# SilentStepStick-TMC2100_v20.net
KiCad netlist of a schematic drawn in EAGLE
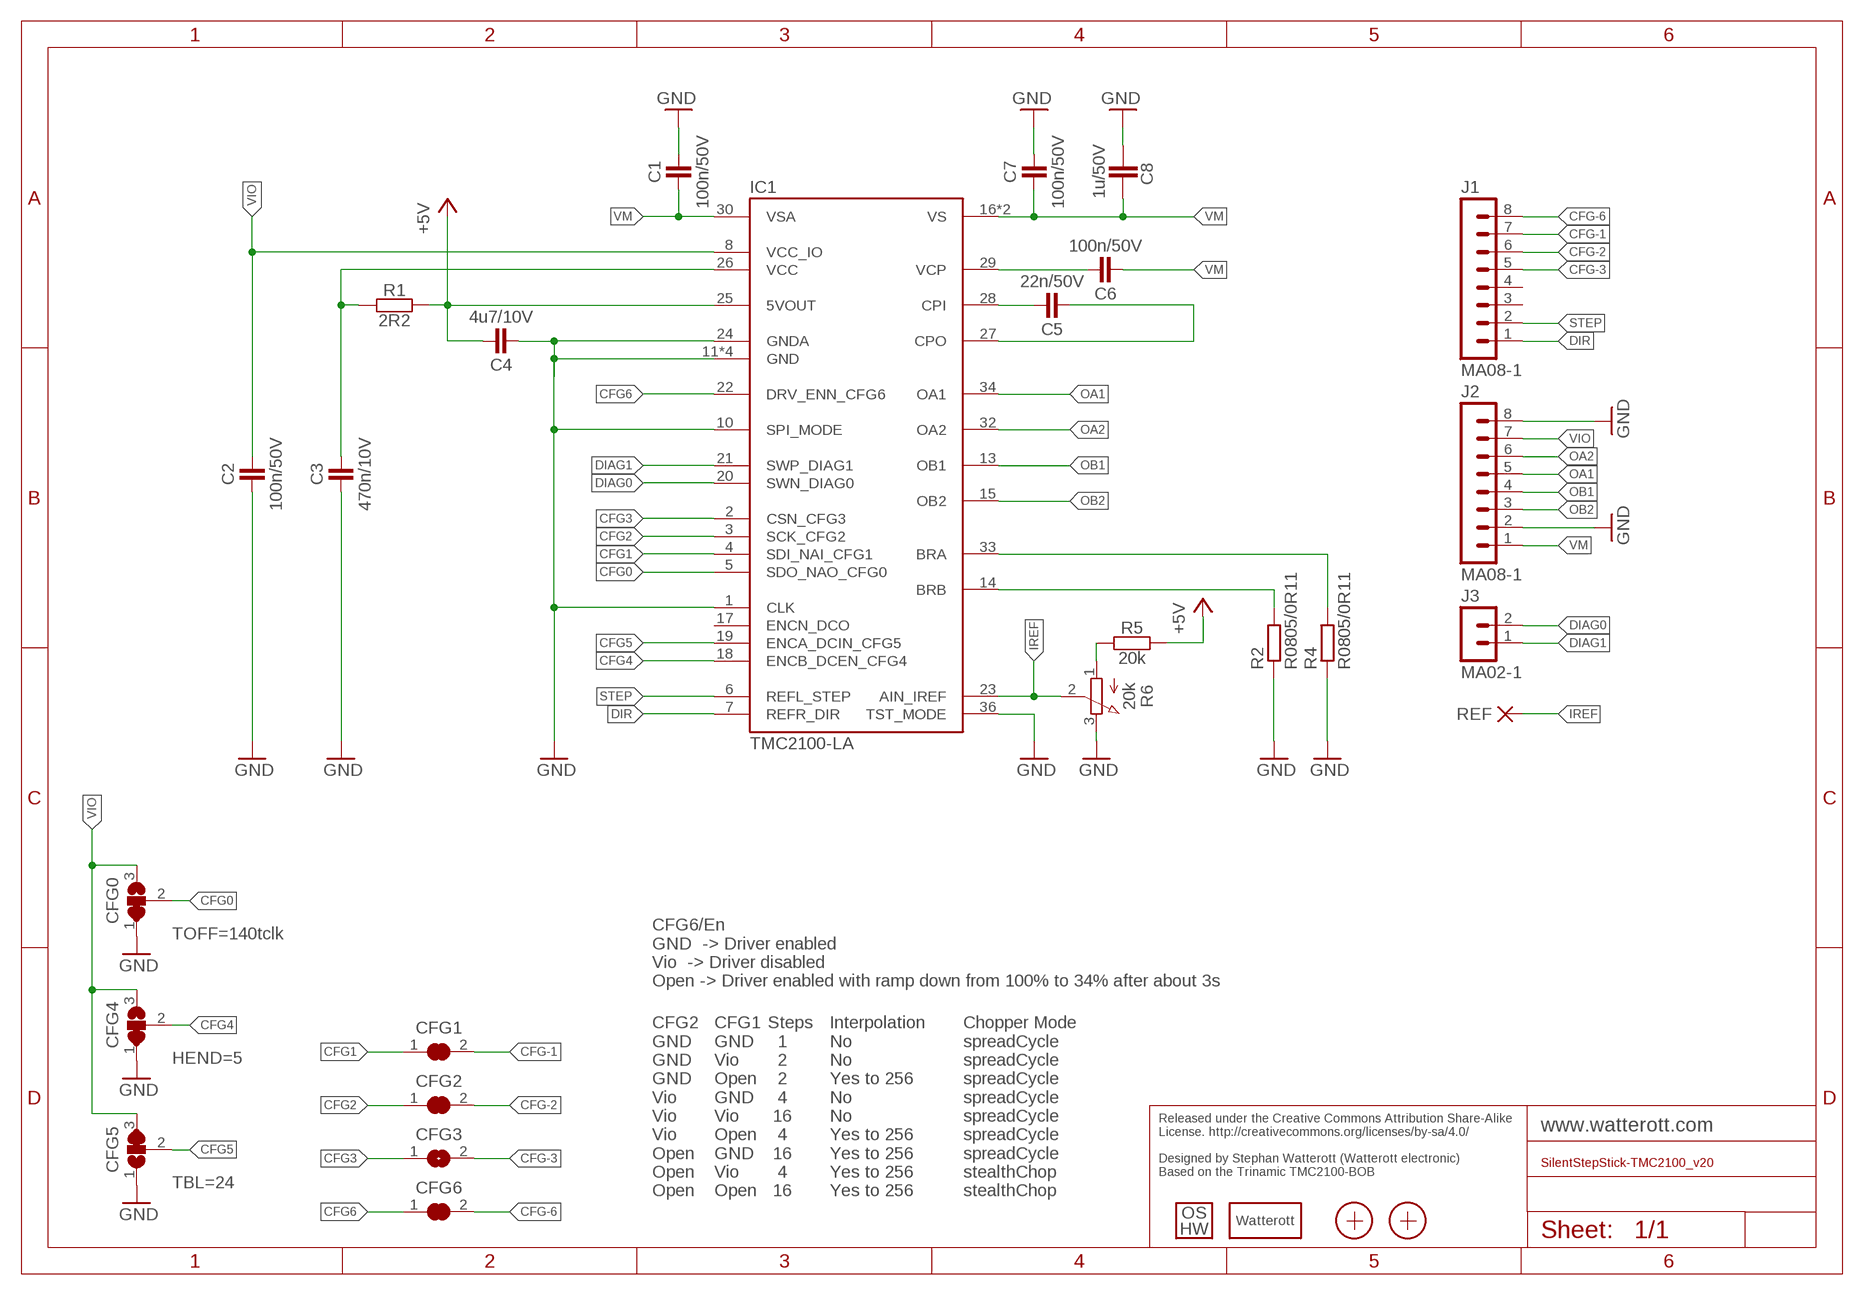
[diagram p0: schematic, sheet 1]

(export (version "E")
  (design (tool "Eeschema 10.0.6"))
  (components
    (comp (ref "C1")
      (value "100n/50V")
      (footprint "eagle-import:C0402")
      (libsource (lib "eagle-import") (part "CAPACITOR-0402"))
    )
    (comp (ref "C2")
      (value "100n/50V")
      (footprint "eagle-import:C0402")
      (libsource (lib "eagle-import") (part "CAPACITOR-0402"))
    )
    (comp (ref "C3")
      (value "470n/10V")
      (footprint "eagle-import:C0402")
      (libsource (lib "eagle-import") (part "CAPACITOR-0402"))
    )
    (comp (ref "C4")
      (value "4u7/10V")
      (footprint "eagle-import:C0402")
      (libsource (lib "eagle-import") (part "CAPACITOR-0402"))
    )
    (comp (ref "C5")
      (value "22n/50V")
      (footprint "eagle-import:C0402")
      (libsource (lib "eagle-import") (part "CAPACITOR-0402"))
    )
    (comp (ref "C6")
      (value "100n/50V")
      (footprint "eagle-import:C0402")
      (libsource (lib "eagle-import") (part "CAPACITOR-0402"))
    )
    (comp (ref "C7")
      (value "100n/50V")
      (footprint "eagle-import:C0402")
      (libsource (lib "eagle-import") (part "CAPACITOR-0402"))
    )
    (comp (ref "C8")
      (value "1u/50V")
      (footprint "eagle-import:C0603")
      (libsource (lib "eagle-import") (part "C-EUC0603"))
    )
    (comp (ref "CFG0")
      (value "JUMPER3-0201")
      (footprint "eagle-import:JUMPER3-0201")
      (libsource (lib "eagle-import") (part "JUMPER3-0201"))
    )
    (comp (ref "CFG1")
      (value "JUMPER2-0201")
      (footprint "eagle-import:JUMPER2-0201")
      (libsource (lib "eagle-import") (part "JUMPER2-0201"))
    )
    (comp (ref "CFG2")
      (value "JUMPER2-0201")
      (footprint "eagle-import:JUMPER2-0201")
      (libsource (lib "eagle-import") (part "JUMPER2-0201"))
    )
    (comp (ref "CFG3")
      (value "JUMPER2-0201")
      (footprint "eagle-import:JUMPER2-0201")
      (libsource (lib "eagle-import") (part "JUMPER2-0201"))
    )
    (comp (ref "CFG4")
      (value "JUMPER3-0201")
      (footprint "eagle-import:JUMPER3-0201")
      (libsource (lib "eagle-import") (part "JUMPER3-0201"))
    )
    (comp (ref "CFG5")
      (value "JUMPER3-0201")
      (footprint "eagle-import:JUMPER3-0201")
      (libsource (lib "eagle-import") (part "JUMPER3-0201"))
    )
    (comp (ref "CFG6")
      (value "JUMPER2-0201")
      (footprint "eagle-import:JUMPER2-0201")
      (libsource (lib "eagle-import") (part "JUMPER2-0201"))
    )
    (comp (ref "IC1")
      (value "TMC2100-LA")
      (footprint "eagle-import:QFN36-PAD")
      (libsource (lib "eagle-import") (part "TMC21X0-LA"))
    )
    (comp (ref "J1")
      (value "MA08-1")
      (footprint "eagle-import:MA08-1")
      (libsource (lib "eagle-import") (part "MA08-1"))
    )
    (comp (ref "J2")
      (value "MA08-1")
      (footprint "eagle-import:MA08-1")
      (libsource (lib "eagle-import") (part "MA08-1"))
    )
    (comp (ref "J3")
      (value "MA02-1")
      (footprint "eagle-import:MA02-1")
      (libsource (lib "eagle-import") (part "MA02-1"))
    )
    (comp (ref "LOGO3")
      (value "LOGO_SPARK-2")
      (footprint "eagle-import:SPARK_2MM")
      (libsource (lib "eagle-import") (part "LOGO_SPARK-2"))
    )
    (comp (ref "LOGO4")
      (value "LOGO_OSHW-2")
      (footprint "eagle-import:OSHW_2MM")
      (libsource (lib "eagle-import") (part "LOGO_OSHW-2"))
    )
    (comp (ref "R1")
      (value "2R2")
      (footprint "eagle-import:C0402")
      (libsource (lib "eagle-import") (part "RESISTOR-0402"))
    )
    (comp (ref "R2")
      (value "R0805/0R11")
      (footprint "eagle-import:M0805")
      (libsource (lib "eagle-import") (part "R-EU_M0805"))
    )
    (comp (ref "R4")
      (value "R0805/0R11")
      (footprint "eagle-import:M0805")
      (libsource (lib "eagle-import") (part "R-EU_M0805"))
    )
    (comp (ref "R5")
      (value "20k")
      (footprint "eagle-import:C0402")
      (libsource (lib "eagle-import") (part "RESISTOR-0402"))
    )
    (comp (ref "R6")
      (value "20k")
      (footprint "eagle-import:POT_EVM3R")
      (libsource (lib "eagle-import") (part "POT-EVM3R"))
    )
    (comp (ref "REF")
      (value "PAD-0.6-1.1")
      (footprint "eagle-import:PAD-0.6-1.1")
      (libsource (lib "eagle-import") (part "PAD-0.6-1.1"))
    )
    (comp (ref "X1")
      (value "PASSER-07")
      (footprint "eagle-import:PASSER_07MM")
      (libsource (lib "eagle-import") (part "PASSER-07"))
    )
    (comp (ref "X2")
      (value "PASSER-07")
      (footprint "eagle-import:PASSER_07MM")
      (libsource (lib "eagle-import") (part "PASSER-07"))
    )
  )
  (nets
    (net (code "1") (name "+5V") (class "Default")
      (node (ref "C4") (pin "2") (pinfunction "2_2") (pintype "passive"))
      (node (ref "IC1") (pin "25") (pinfunction "5VOUT_25") (pintype "power_in"))
      (node (ref "R1") (pin "2") (pinfunction "2_2") (pintype "passive"))
      (node (ref "R5") (pin "2") (pinfunction "2_2") (pintype "passive"))
    )
    (net (code "2") (name "CFG-1") (class "Default")
      (node (ref "CFG1") (pin "2") (pinfunction "2_2") (pintype "passive"))
      (node (ref "J1") (pin "7") (pinfunction "7_7") (pintype "passive"))
    )
    (net (code "3") (name "CFG-2") (class "Default")
      (node (ref "CFG2") (pin "2") (pinfunction "2_2") (pintype "passive"))
      (node (ref "J1") (pin "6") (pinfunction "6_6") (pintype "passive"))
    )
    (net (code "4") (name "CFG-3") (class "Default")
      (node (ref "CFG3") (pin "2") (pinfunction "2_2") (pintype "passive"))
      (node (ref "J1") (pin "5") (pinfunction "5_5") (pintype "passive"))
    )
    (net (code "5") (name "CFG-6") (class "Default")
      (node (ref "CFG6") (pin "2") (pinfunction "2_2") (pintype "passive"))
      (node (ref "J1") (pin "8") (pinfunction "8_8") (pintype "passive"))
    )
    (net (code "6") (name "CFG0") (class "Default")
      (node (ref "CFG0") (pin "2") (pinfunction "2_2") (pintype "passive"))
      (node (ref "IC1") (pin "5") (pinfunction "SDO_NAO_CFG0_5") (pintype "bidirectional"))
    )
    (net (code "7") (name "CFG1") (class "Default")
      (node (ref "CFG1") (pin "1") (pinfunction "1_1") (pintype "passive"))
      (node (ref "IC1") (pin "4") (pinfunction "SDI_NAI_CFG1_4") (pintype "bidirectional"))
    )
    (net (code "8") (name "CFG2") (class "Default")
      (node (ref "CFG2") (pin "1") (pinfunction "1_1") (pintype "passive"))
      (node (ref "IC1") (pin "3") (pinfunction "SCK_CFG2_3") (pintype "bidirectional"))
    )
    (net (code "9") (name "CFG3") (class "Default")
      (node (ref "CFG3") (pin "1") (pinfunction "1_1") (pintype "passive"))
      (node (ref "IC1") (pin "2") (pinfunction "CSN_CFG3_2") (pintype "bidirectional"))
    )
    (net (code "10") (name "CFG4") (class "Default")
      (node (ref "CFG4") (pin "2") (pinfunction "2_2") (pintype "passive"))
      (node (ref "IC1") (pin "18") (pinfunction "ENCB_DCEN_CFG4_18") (pintype "bidirectional"))
    )
    (net (code "11") (name "CFG5") (class "Default")
      (node (ref "CFG5") (pin "2") (pinfunction "2_2") (pintype "passive"))
      (node (ref "IC1") (pin "19") (pinfunction "ENCA_DCIN_CFG5_19") (pintype "bidirectional"))
    )
    (net (code "12") (name "CFG6") (class "Default")
      (node (ref "CFG6") (pin "1") (pinfunction "1_1") (pintype "passive"))
      (node (ref "IC1") (pin "22") (pinfunction "DRV_ENN_CFG6_22") (pintype "bidirectional"))
    )
    (net (code "13") (name "DIAG0") (class "Default")
      (node (ref "IC1") (pin "20") (pinfunction "SWN_DIAG0_20") (pintype "bidirectional"))
      (node (ref "J3") (pin "2") (pinfunction "2_2") (pintype "passive"))
    )
    (net (code "14") (name "DIAG1") (class "Default")
      (node (ref "IC1") (pin "21") (pinfunction "SWP_DIAG1_21") (pintype "bidirectional"))
      (node (ref "J3") (pin "1") (pinfunction "1_1") (pintype "passive"))
    )
    (net (code "15") (name "DIR") (class "Default")
      (node (ref "IC1") (pin "7") (pinfunction "REFR_DIR_7") (pintype "bidirectional"))
      (node (ref "J1") (pin "1") (pinfunction "1_1") (pintype "passive"))
    )
    (net (code "16") (name "GND") (class "Default")
      (node (ref "C1") (pin "2") (pinfunction "2_2") (pintype "passive"))
      (node (ref "C2") (pin "1") (pinfunction "1_1") (pintype "passive"))
      (node (ref "C3") (pin "1") (pinfunction "1_1") (pintype "passive"))
      (node (ref "C4") (pin "1") (pinfunction "1_1") (pintype "passive"))
      (node (ref "C7") (pin "2") (pinfunction "2_2") (pintype "passive"))
      (node (ref "C8") (pin "2") (pinfunction "2_2") (pintype "passive"))
      (node (ref "CFG0") (pin "1") (pinfunction "1_1") (pintype "passive"))
      (node (ref "CFG4") (pin "1") (pinfunction "1_1") (pintype "passive"))
      (node (ref "CFG5") (pin "1") (pinfunction "1_1") (pintype "passive"))
      (node (ref "IC1") (pin "1") (pinfunction "CLK_1") (pintype "bidirectional"))
      (node (ref "IC1") (pin "10") (pinfunction "SPI_MODE_10") (pintype "bidirectional"))
      (node (ref "IC1") (pin "11") (pinfunction "GND_11") (pintype "power_in"))
      (node (ref "IC1") (pin "12") (pinfunction "GND_12") (pintype "power_in"))
      (node (ref "IC1") (pin "24") (pinfunction "GNDA_24") (pintype "power_in"))
      (node (ref "IC1") (pin "35") (pinfunction "GND_35") (pintype "power_in"))
      (node (ref "IC1") (pin "36") (pinfunction "TST_MODE_36") (pintype "bidirectional"))
      (node (ref "IC1") (pin "TP") (pinfunction "GND_TP") (pintype "power_in"))
      (node (ref "J2") (pin "2") (pinfunction "2_2") (pintype "passive"))
      (node (ref "J2") (pin "8") (pinfunction "8_8") (pintype "passive"))
      (node (ref "R2") (pin "1") (pinfunction "1_1") (pintype "passive"))
      (node (ref "R4") (pin "1") (pinfunction "1_1") (pintype "passive"))
      (node (ref "R6") (pin "3") (pinfunction "E_3") (pintype "passive"))
    )
    (net (code "17") (name "IREF") (class "Default")
      (node (ref "IC1") (pin "23") (pinfunction "AIN_IREF_23") (pintype "passive"))
      (node (ref "R6") (pin "2") (pinfunction "S_2") (pintype "passive"))
      (node (ref "REF") (pin "1") (pinfunction "P_1") (pintype "passive"))
    )
    (net (code "18") (name "Net-(IC1-BRA)") (class "Default")
      (node (ref "IC1") (pin "33") (pinfunction "BRA_33") (pintype "output"))
      (node (ref "R4") (pin "2") (pinfunction "2_2") (pintype "passive"))
    )
    (net (code "19") (name "Net-(IC1-BRB)") (class "Default")
      (node (ref "IC1") (pin "14") (pinfunction "BRB_14") (pintype "output"))
      (node (ref "R2") (pin "2") (pinfunction "2_2") (pintype "passive"))
    )
    (net (code "20") (name "Net-(IC1-CPI)") (class "Default")
      (node (ref "C5") (pin "2") (pinfunction "2_2") (pintype "passive"))
      (node (ref "IC1") (pin "28") (pinfunction "CPI_28") (pintype "passive"))
    )
    (net (code "21") (name "Net-(IC1-CPO)") (class "Default")
      (node (ref "C5") (pin "1") (pinfunction "1_1") (pintype "passive"))
      (node (ref "IC1") (pin "27") (pinfunction "CPO_27") (pintype "passive"))
    )
    (net (code "22") (name "Net-(IC1-VCC)") (class "Default")
      (node (ref "C3") (pin "2") (pinfunction "2_2") (pintype "passive"))
      (node (ref "IC1") (pin "26") (pinfunction "VCC_26") (pintype "power_in"))
      (node (ref "R1") (pin "1") (pinfunction "1_1") (pintype "passive"))
    )
    (net (code "23") (name "Net-(IC1-VCP)") (class "Default")
      (node (ref "C6") (pin "2") (pinfunction "2_2") (pintype "passive"))
      (node (ref "IC1") (pin "29") (pinfunction "VCP_29") (pintype "passive"))
    )
    (net (code "24") (name "Net-(R6-A)") (class "Default")
      (node (ref "R5") (pin "1") (pinfunction "1_1") (pintype "passive"))
      (node (ref "R6") (pin "1") (pinfunction "A_1") (pintype "passive"))
    )
    (net (code "25") (name "OA1") (class "Default")
      (node (ref "IC1") (pin "34") (pinfunction "OA1_34") (pintype "output"))
      (node (ref "J2") (pin "5") (pinfunction "5_5") (pintype "passive"))
    )
    (net (code "26") (name "OA2") (class "Default")
      (node (ref "IC1") (pin "32") (pinfunction "OA2_32") (pintype "output"))
      (node (ref "J2") (pin "6") (pinfunction "6_6") (pintype "passive"))
    )
    (net (code "27") (name "OB1") (class "Default")
      (node (ref "IC1") (pin "13") (pinfunction "OB1_13") (pintype "output"))
      (node (ref "J2") (pin "4") (pinfunction "4_4") (pintype "passive"))
    )
    (net (code "28") (name "OB2") (class "Default")
      (node (ref "IC1") (pin "15") (pinfunction "OB2_15") (pintype "output"))
      (node (ref "J2") (pin "3") (pinfunction "3_3") (pintype "passive"))
    )
    (net (code "29") (name "STEP") (class "Default")
      (node (ref "IC1") (pin "6") (pinfunction "REFL_STEP_6") (pintype "bidirectional"))
      (node (ref "J1") (pin "2") (pinfunction "2_2") (pintype "passive"))
    )
    (net (code "30") (name "VIO") (class "Default")
      (node (ref "C2") (pin "2") (pinfunction "2_2") (pintype "passive"))
      (node (ref "CFG0") (pin "3") (pinfunction "3_3") (pintype "passive"))
      (node (ref "CFG4") (pin "3") (pinfunction "3_3") (pintype "passive"))
      (node (ref "CFG5") (pin "3") (pinfunction "3_3") (pintype "passive"))
      (node (ref "IC1") (pin "8") (pinfunction "VCC_IO_8") (pintype "power_in"))
      (node (ref "J2") (pin "7") (pinfunction "7_7") (pintype "passive"))
    )
    (net (code "31") (name "VM") (class "Default")
      (node (ref "C1") (pin "1") (pinfunction "1_1") (pintype "passive"))
      (node (ref "C6") (pin "1") (pinfunction "1_1") (pintype "passive"))
      (node (ref "C7") (pin "1") (pinfunction "1_1") (pintype "passive"))
      (node (ref "C8") (pin "1") (pinfunction "1_1") (pintype "passive"))
      (node (ref "IC1") (pin "16") (pinfunction "VS_16") (pintype "power_in"))
      (node (ref "IC1") (pin "30") (pinfunction "VSA_30") (pintype "power_in"))
      (node (ref "IC1") (pin "31") (pinfunction "VS_31") (pintype "power_in"))
      (node (ref "J2") (pin "1") (pinfunction "1_1") (pintype "passive"))
    )
    (net (code "32") (name "unconnected-(IC1-ENCN_DCO-Pad17)") (class "Default")
      (node (ref "IC1") (pin "17") (pinfunction "ENCN_DCO_17") (pintype "bidirectional"))
    )
    (net (code "33") (name "unconnected-(J1-Pad3)") (class "Default")
      (node (ref "J1") (pin "3") (pinfunction "3_3") (pintype "passive"))
    )
    (net (code "34") (name "unconnected-(J1-Pad4)") (class "Default")
      (node (ref "J1") (pin "4") (pinfunction "4_4") (pintype "passive"))
    )
  )
)
